# LED_IoT_Card.net
KiCad netlist of a schematic drawn in EAGLE
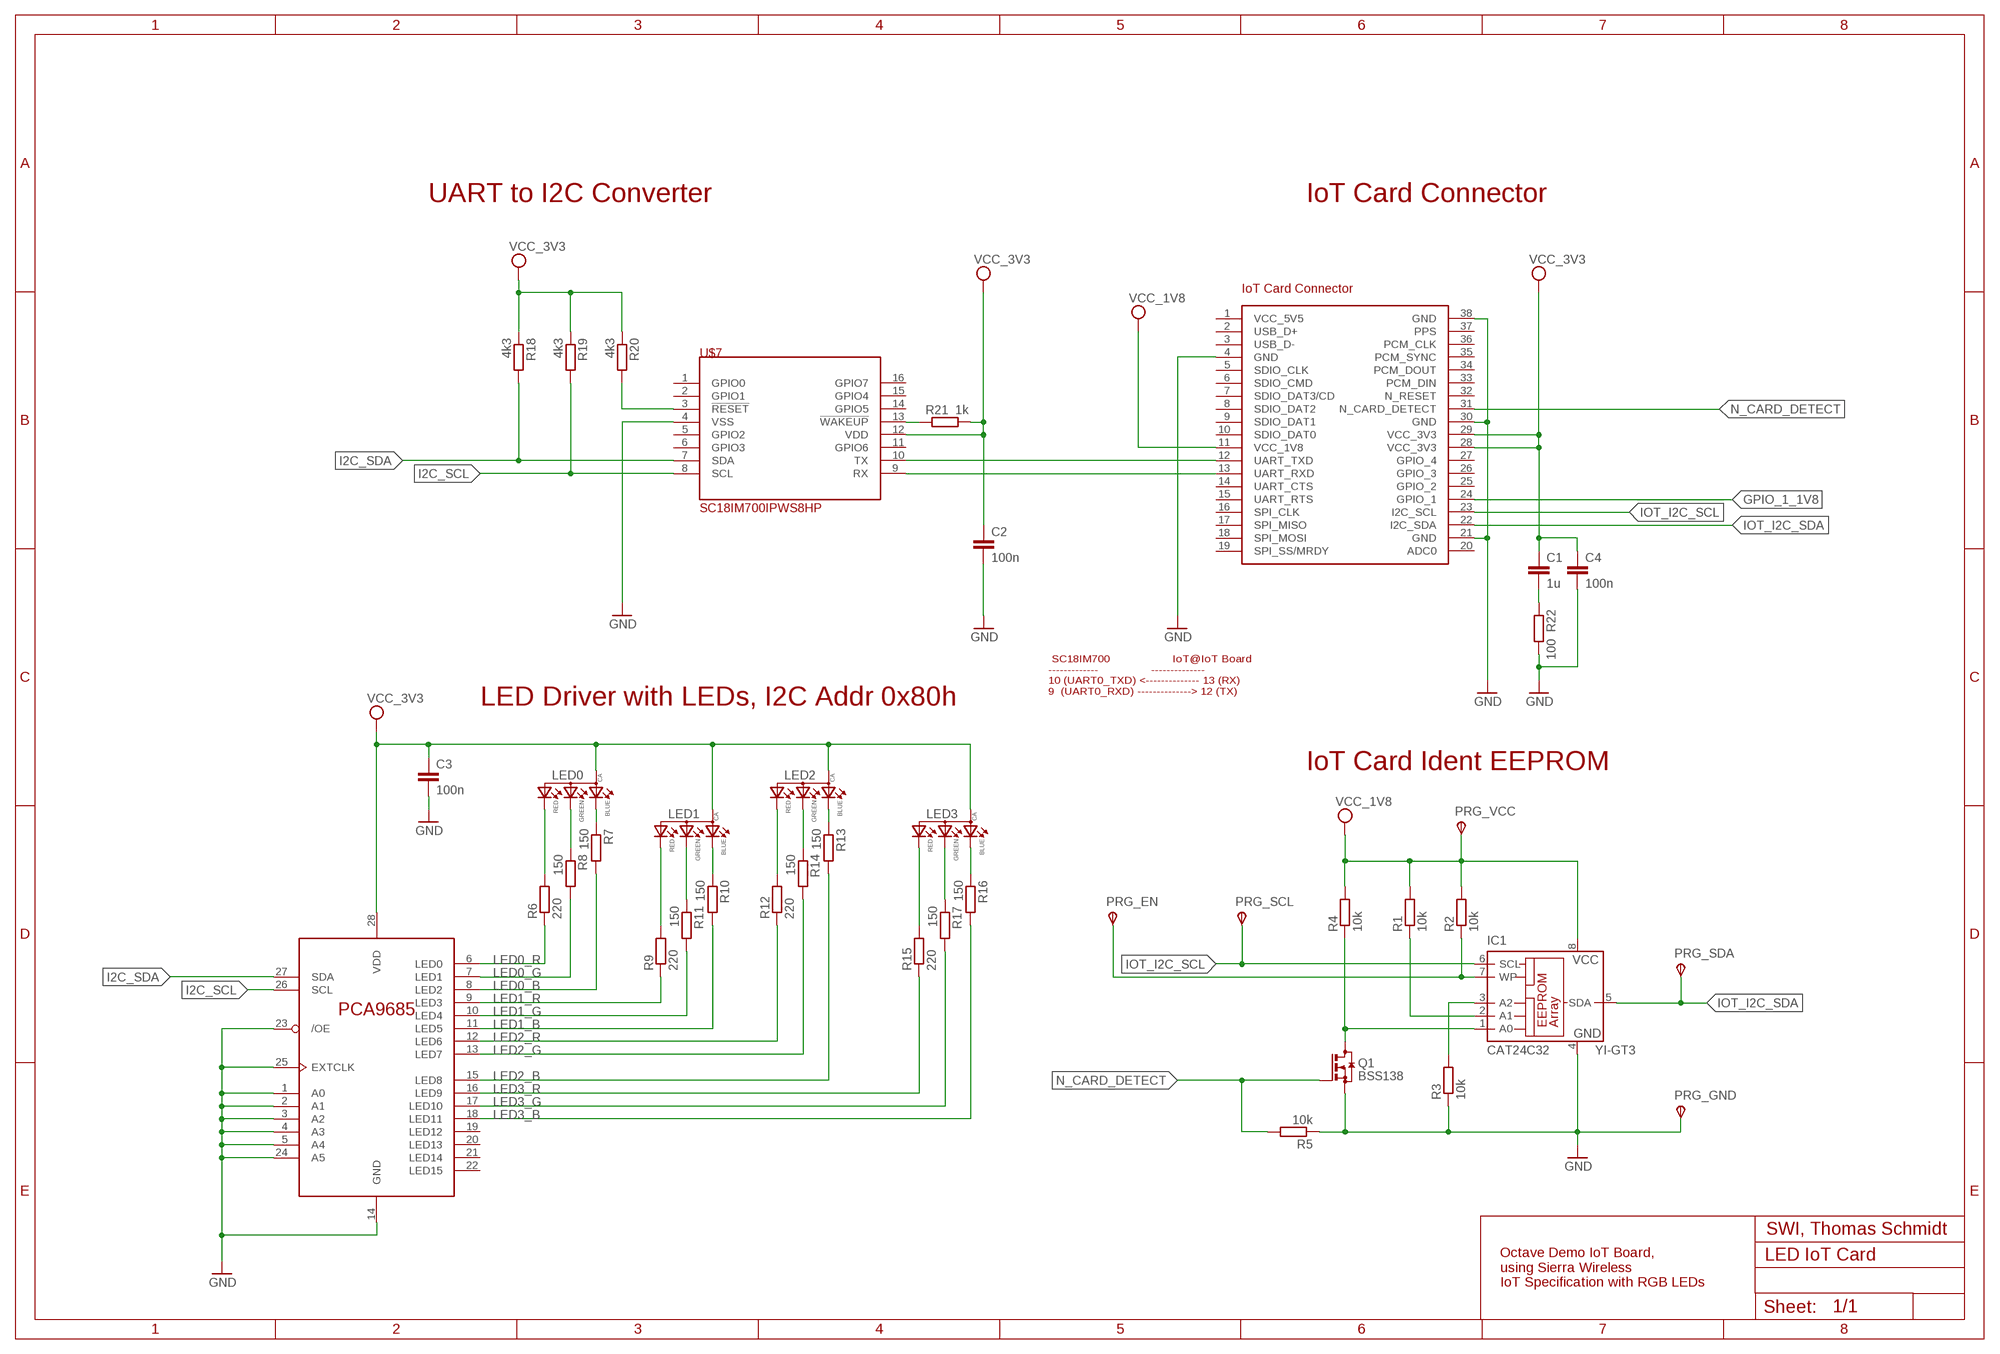
[diagram p0: schematic, sheet 1]

(export (version "E")
  (design (tool "Eeschema 10.0.6"))
  (components
    (comp (ref "C1")
      (value "1u")
      (footprint "eagle-import:C0805K")
      (libsource (lib "eagle-import") (part "C-EUC0805K"))
    )
    (comp (ref "C2")
      (value "100n")
      (footprint "eagle-import:C0603K")
      (libsource (lib "eagle-import") (part "C-EUC0603K"))
    )
    (comp (ref "C3")
      (value "100n")
      (footprint "eagle-import:C0603K")
      (libsource (lib "eagle-import") (part "C-EUC0603K"))
    )
    (comp (ref "C4")
      (value "100n")
      (footprint "eagle-import:C0603K")
      (libsource (lib "eagle-import") (part "C-EUC0603K"))
    )
    (comp (ref "IC1")
      (value "CAT24C32 YI-GT3")
      (footprint "eagle-import:TSSOP8")
      (fields (field (name "MPN") "CAT24C64YI-GT3"))
      (libsource (lib "eagle-import") (part "24STC64"))
    )
    (comp (ref "LED0")
      (value "0.13_RGB_LEDPLCC")
      (footprint "eagle-import:P-LCC-4-3")
      (libsource (lib "eagle-import") (part "0.13_RGB_LEDPLCC"))
    )
    (comp (ref "LED1")
      (value "0.13_RGB_LEDPLCC")
      (footprint "eagle-import:P-LCC-4-3")
      (libsource (lib "eagle-import") (part "0.13_RGB_LEDPLCC"))
    )
    (comp (ref "LED2")
      (value "0.13_RGB_LEDPLCC")
      (footprint "eagle-import:P-LCC-4-3")
      (libsource (lib "eagle-import") (part "0.13_RGB_LEDPLCC"))
    )
    (comp (ref "LED3")
      (value "0.13_RGB_LEDPLCC")
      (footprint "eagle-import:P-LCC-4-3")
      (libsource (lib "eagle-import") (part "0.13_RGB_LEDPLCC"))
    )
    (comp (ref "PRG_EN")
      (value "TPSB1,27")
      (footprint "eagle-import:B1,27")
      (libsource (lib "eagle-import") (part "TPSB1,27"))
    )
    (comp (ref "PRG_GND")
      (value "TPSB1,27")
      (footprint "eagle-import:B1,27")
      (libsource (lib "eagle-import") (part "TPSB1,27"))
    )
    (comp (ref "PRG_SCL")
      (value "TPSB1,27")
      (footprint "eagle-import:B1,27")
      (libsource (lib "eagle-import") (part "TPSB1,27"))
    )
    (comp (ref "PRG_SDA")
      (value "TPSB1,27")
      (footprint "eagle-import:B1,27")
      (libsource (lib "eagle-import") (part "TPSB1,27"))
    )
    (comp (ref "PRG_VCC")
      (value "TPSB1,27")
      (footprint "eagle-import:B1,27")
      (libsource (lib "eagle-import") (part "TPSB1,27"))
    )
    (comp (ref "Q1")
      (value "BSS138")
      (footprint "eagle-import:SOT23")
      (libsource (lib "eagle-import") (part "BSS123"))
    )
    (comp (ref "R1")
      (value "10k")
      (footprint "eagle-import:R0402")
      (libsource (lib "eagle-import") (part "R-EU_R0402"))
    )
    (comp (ref "R2")
      (value "10k")
      (footprint "eagle-import:R0402")
      (libsource (lib "eagle-import") (part "R-EU_R0402"))
    )
    (comp (ref "R3")
      (value "10k")
      (footprint "eagle-import:R0402")
      (libsource (lib "eagle-import") (part "R-EU_R0402"))
    )
    (comp (ref "R4")
      (value "10k")
      (footprint "eagle-import:R0402")
      (libsource (lib "eagle-import") (part "R-EU_R0402"))
    )
    (comp (ref "R5")
      (value "10k")
      (footprint "eagle-import:R0402")
      (libsource (lib "eagle-import") (part "R-EU_R0402"))
    )
    (comp (ref "R6")
      (value "220")
      (footprint "eagle-import:R0402")
      (libsource (lib "eagle-import") (part "R-EU_R0402"))
    )
    (comp (ref "R7")
      (value "150")
      (footprint "eagle-import:R0402")
      (libsource (lib "eagle-import") (part "R-EU_R0402"))
    )
    (comp (ref "R8")
      (value "150")
      (footprint "eagle-import:R0402")
      (libsource (lib "eagle-import") (part "R-EU_R0402"))
    )
    (comp (ref "R9")
      (value "220")
      (footprint "eagle-import:R0402")
      (libsource (lib "eagle-import") (part "R-EU_R0402"))
    )
    (comp (ref "R10")
      (value "150")
      (footprint "eagle-import:R0402")
      (libsource (lib "eagle-import") (part "R-EU_R0402"))
    )
    (comp (ref "R11")
      (value "150")
      (footprint "eagle-import:R0402")
      (libsource (lib "eagle-import") (part "R-EU_R0402"))
    )
    (comp (ref "R12")
      (value "220")
      (footprint "eagle-import:R0402")
      (libsource (lib "eagle-import") (part "R-EU_R0402"))
    )
    (comp (ref "R13")
      (value "150")
      (footprint "eagle-import:R0402")
      (libsource (lib "eagle-import") (part "R-EU_R0402"))
    )
    (comp (ref "R14")
      (value "150")
      (footprint "eagle-import:R0402")
      (libsource (lib "eagle-import") (part "R-EU_R0402"))
    )
    (comp (ref "R15")
      (value "220")
      (footprint "eagle-import:R0402")
      (libsource (lib "eagle-import") (part "R-EU_R0402"))
    )
    (comp (ref "R16")
      (value "150")
      (footprint "eagle-import:R0402")
      (libsource (lib "eagle-import") (part "R-EU_R0402"))
    )
    (comp (ref "R17")
      (value "150")
      (footprint "eagle-import:R0402")
      (libsource (lib "eagle-import") (part "R-EU_R0402"))
    )
    (comp (ref "R18")
      (value "4k3")
      (footprint "eagle-import:R0402")
      (libsource (lib "eagle-import") (part "R-EU_R0402"))
    )
    (comp (ref "R19")
      (value "4k3")
      (footprint "eagle-import:R0402")
      (libsource (lib "eagle-import") (part "R-EU_R0402"))
    )
    (comp (ref "R20")
      (value "4k3")
      (footprint "eagle-import:R0402")
      (libsource (lib "eagle-import") (part "R-EU_R0402"))
    )
    (comp (ref "R21")
      (value "1k")
      (footprint "eagle-import:R0402")
      (libsource (lib "eagle-import") (part "R-EU_R0402"))
    )
    (comp (ref "R22")
      (value "100")
      (footprint "eagle-import:R0402")
      (libsource (lib "eagle-import") (part "R-EU_R0402"))
    )
    (comp (ref "U$1")
      (value "IOTLONG")
      (footprint "eagle-import:IOT_LONG")
      (libsource (lib "eagle-import") (part "IOTLONG"))
    )
    (comp (ref "U$2")
      (value "PCA9685PW")
      (footprint "eagle-import:TSSOP28")
      (libsource (lib "eagle-import") (part "PCA9685PW"))
    )
    (comp (ref "U$7")
      (value "SC18IM700IPWS8HP")
      (footprint "eagle-import:TSSOP16")
      (libsource (lib "eagle-import") (part "SC18IM700IPWS8HP"))
    )
  )
  (nets
    (net (code "1") (name "/LED0_B") (class "Default")
      (node (ref "R7") (pin "2") (pinfunction "2_2") (pintype "passive"))
      (node (ref "U$2") (pin "8") (pinfunction "LED2_8") (pintype "bidirectional"))
    )
    (net (code "2") (name "/LED0_G") (class "Default")
      (node (ref "R8") (pin "2") (pinfunction "2_2") (pintype "passive"))
      (node (ref "U$2") (pin "7") (pinfunction "LED1_7") (pintype "bidirectional"))
    )
    (net (code "3") (name "/LED0_R") (class "Default")
      (node (ref "R6") (pin "1") (pinfunction "1_1") (pintype "passive"))
      (node (ref "U$2") (pin "6") (pinfunction "LED0_6") (pintype "bidirectional"))
    )
    (net (code "4") (name "/LED1_B") (class "Default")
      (node (ref "R10") (pin "2") (pinfunction "2_2") (pintype "passive"))
      (node (ref "U$2") (pin "11") (pinfunction "LED5_11") (pintype "bidirectional"))
    )
    (net (code "5") (name "/LED1_G") (class "Default")
      (node (ref "R11") (pin "2") (pinfunction "2_2") (pintype "passive"))
      (node (ref "U$2") (pin "10") (pinfunction "LED4_10") (pintype "bidirectional"))
    )
    (net (code "6") (name "/LED1_R") (class "Default")
      (node (ref "R9") (pin "1") (pinfunction "1_1") (pintype "passive"))
      (node (ref "U$2") (pin "9") (pinfunction "LED3_9") (pintype "bidirectional"))
    )
    (net (code "7") (name "/LED2_B") (class "Default")
      (node (ref "R13") (pin "2") (pinfunction "2_2") (pintype "passive"))
      (node (ref "U$2") (pin "15") (pinfunction "LED8_15") (pintype "bidirectional"))
    )
    (net (code "8") (name "/LED2_G") (class "Default")
      (node (ref "R14") (pin "2") (pinfunction "2_2") (pintype "passive"))
      (node (ref "U$2") (pin "13") (pinfunction "LED7_13") (pintype "bidirectional"))
    )
    (net (code "9") (name "/LED2_R") (class "Default")
      (node (ref "R12") (pin "1") (pinfunction "1_1") (pintype "passive"))
      (node (ref "U$2") (pin "12") (pinfunction "LED6_12") (pintype "bidirectional"))
    )
    (net (code "10") (name "/LED3_B") (class "Default")
      (node (ref "R16") (pin "2") (pinfunction "2_2") (pintype "passive"))
      (node (ref "U$2") (pin "18") (pinfunction "LED11_18") (pintype "bidirectional"))
    )
    (net (code "11") (name "/LED3_G") (class "Default")
      (node (ref "R17") (pin "2") (pinfunction "2_2") (pintype "passive"))
      (node (ref "U$2") (pin "17") (pinfunction "LED10_17") (pintype "bidirectional"))
    )
    (net (code "12") (name "/LED3_R") (class "Default")
      (node (ref "R15") (pin "1") (pinfunction "1_1") (pintype "passive"))
      (node (ref "U$2") (pin "16") (pinfunction "LED9_16") (pintype "bidirectional"))
    )
    (net (code "13") (name "/VCC_5V5") (class "Default")
      (node (ref "U$1") (pin "1") (pinfunction "VCC_5V5_1") (pintype "power_in"))
    )
    (net (code "14") (name "GND") (class "Default")
      (node (ref "C2") (pin "2") (pinfunction "2_2") (pintype "passive"))
      (node (ref "C3") (pin "2") (pinfunction "2_2") (pintype "passive"))
      (node (ref "C4") (pin "2") (pinfunction "2_2") (pintype "passive"))
      (node (ref "IC1") (pin "4") (pinfunction "GND_4") (pintype "power_in"))
      (node (ref "PRG_GND") (pin "TP") (pinfunction "PP_TP") (pintype "input"))
      (node (ref "Q1") (pin "2") (pinfunction "S_2") (pintype "passive"))
      (node (ref "R22") (pin "2") (pinfunction "2_2") (pintype "passive"))
      (node (ref "R3") (pin "1") (pinfunction "1_1") (pintype "passive"))
      (node (ref "R5") (pin "1") (pinfunction "1_1") (pintype "passive"))
      (node (ref "U$1") (pin "21") (pinfunction "GND_21") (pintype "power_in"))
      (node (ref "U$1") (pin "30") (pinfunction "GND_30") (pintype "power_in"))
      (node (ref "U$1") (pin "38") (pinfunction "GND_38") (pintype "bidirectional"))
      (node (ref "U$1") (pin "4") (pinfunction "GND_4") (pintype "power_in"))
      (node (ref "U$2") (pin "1") (pinfunction "A0_1") (pintype "bidirectional"))
      (node (ref "U$2") (pin "14") (pinfunction "GND_14") (pintype "power_in"))
      (node (ref "U$2") (pin "2") (pinfunction "A1_2") (pintype "bidirectional"))
      (node (ref "U$2") (pin "23") (pinfunction "/OE_23") (pintype "bidirectional"))
      (node (ref "U$2") (pin "24") (pinfunction "A5_24") (pintype "bidirectional"))
      (node (ref "U$2") (pin "25") (pinfunction "EXTCLK_25") (pintype "input"))
      (node (ref "U$2") (pin "3") (pinfunction "A2_3") (pintype "bidirectional"))
      (node (ref "U$2") (pin "4") (pinfunction "A3_4") (pintype "bidirectional"))
      (node (ref "U$2") (pin "5") (pinfunction "A4_5") (pintype "bidirectional"))
      (node (ref "U$7") (pin "4") (pinfunction "VSS_4") (pintype "power_in"))
    )
    (net (code "15") (name "GPIO_1_1V8") (class "Default")
      (node (ref "U$1") (pin "24") (pinfunction "GPIO_1_24") (pintype "bidirectional"))
    )
    (net (code "16") (name "I2C_SCL") (class "Default")
      (node (ref "R19") (pin "2") (pinfunction "2_2") (pintype "passive"))
      (node (ref "U$2") (pin "26") (pinfunction "SCL_26") (pintype "bidirectional"))
      (node (ref "U$7") (pin "8") (pinfunction "SCL_8") (pintype "bidirectional"))
    )
    (net (code "17") (name "I2C_SDA") (class "Default")
      (node (ref "R18") (pin "2") (pinfunction "2_2") (pintype "passive"))
      (node (ref "U$2") (pin "27") (pinfunction "SDA_27") (pintype "bidirectional"))
      (node (ref "U$7") (pin "7") (pinfunction "SDA_7") (pintype "bidirectional"))
    )
    (net (code "18") (name "IOT_I2C_SCL") (class "Default")
      (node (ref "IC1") (pin "6") (pinfunction "SCL_6") (pintype "input"))
      (node (ref "PRG_SCL") (pin "TP") (pinfunction "PP_TP") (pintype "input"))
      (node (ref "U$1") (pin "23") (pinfunction "I2C_SCL_23") (pintype "input"))
    )
    (net (code "19") (name "IOT_I2C_SDA") (class "Default")
      (node (ref "IC1") (pin "5") (pinfunction "SDA_5") (pintype "bidirectional"))
      (node (ref "PRG_SDA") (pin "TP") (pinfunction "PP_TP") (pintype "input"))
      (node (ref "U$1") (pin "22") (pinfunction "I2C_SDA_22") (pintype "bidirectional"))
    )
    (net (code "20") (name "N_CARD_DETECT") (class "Default")
      (node (ref "Q1") (pin "1") (pinfunction "G_1") (pintype "passive"))
      (node (ref "R5") (pin "2") (pinfunction "2_2") (pintype "passive"))
      (node (ref "U$1") (pin "31") (pinfunction "N_CARD_DETECT_31") (pintype "bidirectional"))
    )
    (net (code "21") (name "Net-(C1-Pad2)") (class "Default")
      (node (ref "C1") (pin "2") (pinfunction "2_2") (pintype "passive"))
      (node (ref "R22") (pin "1") (pinfunction "1_1") (pintype "passive"))
    )
    (net (code "22") (name "Net-(IC1-A0)") (class "Default")
      (node (ref "IC1") (pin "1") (pinfunction "A0_1") (pintype "input"))
      (node (ref "Q1") (pin "3") (pinfunction "D_3") (pintype "passive"))
      (node (ref "R4") (pin "1") (pinfunction "1_1") (pintype "passive"))
    )
    (net (code "23") (name "Net-(IC1-A1)") (class "Default")
      (node (ref "IC1") (pin "2") (pinfunction "A1_2") (pintype "input"))
      (node (ref "R1") (pin "1") (pinfunction "1_1") (pintype "passive"))
    )
    (net (code "24") (name "Net-(IC1-A2)") (class "Default")
      (node (ref "IC1") (pin "3") (pinfunction "A2_3") (pintype "input"))
      (node (ref "R3") (pin "2") (pinfunction "2_2") (pintype "passive"))
    )
    (net (code "25") (name "Net-(IC1-WP)") (class "Default")
      (node (ref "IC1") (pin "7") (pinfunction "WP_7") (pintype "input"))
      (node (ref "PRG_EN") (pin "TP") (pinfunction "PP_TP") (pintype "input"))
      (node (ref "R2") (pin "1") (pinfunction "1_1") (pintype "passive"))
    )
    (net (code "26") (name "Net-(LED0-BLUE)") (class "Default")
      (node (ref "LED0") (pin "3") (pinfunction "BLUE_3") (pintype "passive"))
      (node (ref "R7") (pin "1") (pinfunction "1_1") (pintype "passive"))
    )
    (net (code "27") (name "Net-(LED0-GREEN)") (class "Default")
      (node (ref "LED0") (pin "2") (pinfunction "GREEN_2") (pintype "passive"))
      (node (ref "R8") (pin "1") (pinfunction "1_1") (pintype "passive"))
    )
    (net (code "28") (name "Net-(LED0-RED)") (class "Default")
      (node (ref "LED0") (pin "1") (pinfunction "RED_1") (pintype "passive"))
      (node (ref "R6") (pin "2") (pinfunction "2_2") (pintype "passive"))
    )
    (net (code "29") (name "Net-(LED1-BLUE)") (class "Default")
      (node (ref "LED1") (pin "3") (pinfunction "BLUE_3") (pintype "passive"))
      (node (ref "R10") (pin "1") (pinfunction "1_1") (pintype "passive"))
    )
    (net (code "30") (name "Net-(LED1-GREEN)") (class "Default")
      (node (ref "LED1") (pin "2") (pinfunction "GREEN_2") (pintype "passive"))
      (node (ref "R11") (pin "1") (pinfunction "1_1") (pintype "passive"))
    )
    (net (code "31") (name "Net-(LED1-RED)") (class "Default")
      (node (ref "LED1") (pin "1") (pinfunction "RED_1") (pintype "passive"))
      (node (ref "R9") (pin "2") (pinfunction "2_2") (pintype "passive"))
    )
    (net (code "32") (name "Net-(LED2-BLUE)") (class "Default")
      (node (ref "LED2") (pin "3") (pinfunction "BLUE_3") (pintype "passive"))
      (node (ref "R13") (pin "1") (pinfunction "1_1") (pintype "passive"))
    )
    (net (code "33") (name "Net-(LED2-GREEN)") (class "Default")
      (node (ref "LED2") (pin "2") (pinfunction "GREEN_2") (pintype "passive"))
      (node (ref "R14") (pin "1") (pinfunction "1_1") (pintype "passive"))
    )
    (net (code "34") (name "Net-(LED2-RED)") (class "Default")
      (node (ref "LED2") (pin "1") (pinfunction "RED_1") (pintype "passive"))
      (node (ref "R12") (pin "2") (pinfunction "2_2") (pintype "passive"))
    )
    (net (code "35") (name "Net-(LED3-BLUE)") (class "Default")
      (node (ref "LED3") (pin "3") (pinfunction "BLUE_3") (pintype "passive"))
      (node (ref "R16") (pin "1") (pinfunction "1_1") (pintype "passive"))
    )
    (net (code "36") (name "Net-(LED3-GREEN)") (class "Default")
      (node (ref "LED3") (pin "2") (pinfunction "GREEN_2") (pintype "passive"))
      (node (ref "R17") (pin "1") (pinfunction "1_1") (pintype "passive"))
    )
    (net (code "37") (name "Net-(LED3-RED)") (class "Default")
      (node (ref "LED3") (pin "1") (pinfunction "RED_1") (pintype "passive"))
      (node (ref "R15") (pin "2") (pinfunction "2_2") (pintype "passive"))
    )
    (net (code "38") (name "Net-(U$1-UART_RXD)") (class "Default")
      (node (ref "U$1") (pin "13") (pinfunction "UART_RXD_13") (pintype "input"))
      (node (ref "U$7") (pin "9") (pinfunction "RX_9") (pintype "bidirectional"))
    )
    (net (code "39") (name "Net-(U$1-UART_TXD)") (class "Default")
      (node (ref "U$1") (pin "12") (pinfunction "UART_TXD_12") (pintype "output"))
      (node (ref "U$7") (pin "10") (pinfunction "TX_10") (pintype "bidirectional"))
    )
    (net (code "40") (name "Net-(U$7-~{RESET})") (class "Default")
      (node (ref "R20") (pin "2") (pinfunction "2_2") (pintype "passive"))
      (node (ref "U$7") (pin "3") (pinfunction "~{RESET}_3") (pintype "bidirectional"))
    )
    (net (code "41") (name "Net-(U$7-~{WAKEUP})") (class "Default")
      (node (ref "R21") (pin "1") (pinfunction "1_1") (pintype "passive"))
      (node (ref "U$7") (pin "13") (pinfunction "~{WAKEUP}_13") (pintype "bidirectional"))
    )
    (net (code "42") (name "VCC_1V8") (class "Default")
      (node (ref "IC1") (pin "8") (pinfunction "VCC_8") (pintype "power_in"))
      (node (ref "PRG_VCC") (pin "TP") (pinfunction "PP_TP") (pintype "input"))
      (node (ref "R1") (pin "2") (pinfunction "2_2") (pintype "passive"))
      (node (ref "R2") (pin "2") (pinfunction "2_2") (pintype "passive"))
      (node (ref "R4") (pin "2") (pinfunction "2_2") (pintype "passive"))
      (node (ref "U$1") (pin "11") (pinfunction "VCC_1V8_11") (pintype "power_in"))
    )
    (net (code "43") (name "VCC_3V3") (class "Default")
      (node (ref "C1") (pin "1") (pinfunction "1_1") (pintype "passive"))
      (node (ref "C2") (pin "1") (pinfunction "1_1") (pintype "passive"))
      (node (ref "C3") (pin "1") (pinfunction "1_1") (pintype "passive"))
      (node (ref "C4") (pin "1") (pinfunction "1_1") (pintype "passive"))
      (node (ref "LED0") (pin "4") (pinfunction "ANODE_4") (pintype "passive"))
      (node (ref "LED1") (pin "4") (pinfunction "ANODE_4") (pintype "passive"))
      (node (ref "LED2") (pin "4") (pinfunction "ANODE_4") (pintype "passive"))
      (node (ref "LED3") (pin "4") (pinfunction "ANODE_4") (pintype "passive"))
      (node (ref "R18") (pin "1") (pinfunction "1_1") (pintype "passive"))
      (node (ref "R19") (pin "1") (pinfunction "1_1") (pintype "passive"))
      (node (ref "R20") (pin "1") (pinfunction "1_1") (pintype "passive"))
      (node (ref "R21") (pin "2") (pinfunction "2_2") (pintype "passive"))
      (node (ref "U$1") (pin "28") (pinfunction "VCC_3V3_28") (pintype "power_in"))
      (node (ref "U$1") (pin "29") (pinfunction "VCC_3V3_29") (pintype "power_in"))
      (node (ref "U$2") (pin "28") (pinfunction "VDD_28") (pintype "power_in"))
      (node (ref "U$7") (pin "12") (pinfunction "VDD_12") (pintype "power_in"))
    )
    (net (code "44") (name "unconnected-(U$1-ADC0-Pad20)") (class "Default")
      (node (ref "U$1") (pin "20") (pinfunction "ADC0_20") (pintype "output"))
    )
    (net (code "45") (name "unconnected-(U$1-GPIO_2-Pad25)") (class "Default")
      (node (ref "U$1") (pin "25") (pinfunction "GPIO_2_25") (pintype "bidirectional"))
    )
    (net (code "46") (name "unconnected-(U$1-GPIO_3-Pad26)") (class "Default")
      (node (ref "U$1") (pin "26") (pinfunction "GPIO_3_26") (pintype "bidirectional"))
    )
    (net (code "47") (name "unconnected-(U$1-GPIO_4-Pad27)") (class "Default")
      (node (ref "U$1") (pin "27") (pinfunction "GPIO_4_27") (pintype "bidirectional"))
    )
    (net (code "48") (name "unconnected-(U$1-N_RESET-Pad32)") (class "Default")
      (node (ref "U$1") (pin "32") (pinfunction "N_RESET_32") (pintype "bidirectional"))
    )
    (net (code "49") (name "unconnected-(U$1-PCM_CLK-Pad36)") (class "Default")
      (node (ref "U$1") (pin "36") (pinfunction "PCM_CLK_36") (pintype "input"))
    )
    (net (code "50") (name "unconnected-(U$1-PCM_DIN-Pad33)") (class "Default")
      (node (ref "U$1") (pin "33") (pinfunction "PCM_DIN_33") (pintype "output"))
    )
    (net (code "51") (name "unconnected-(U$1-PCM_DOUT-Pad34)") (class "Default")
      (node (ref "U$1") (pin "34") (pinfunction "PCM_DOUT_34") (pintype "input"))
    )
    (net (code "52") (name "unconnected-(U$1-PCM_SYNC-Pad35)") (class "Default")
      (node (ref "U$1") (pin "35") (pinfunction "PCM_SYNC_35") (pintype "input"))
    )
    (net (code "53") (name "unconnected-(U$1-PPS-Pad37)") (class "Default")
      (node (ref "U$1") (pin "37") (pinfunction "PPS_37") (pintype "input"))
    )
    (net (code "54") (name "unconnected-(U$1-SDIO_CLK-Pad5)") (class "Default")
      (node (ref "U$1") (pin "5") (pinfunction "SDIO_CLK_5") (pintype "input"))
    )
    (net (code "55") (name "unconnected-(U$1-SDIO_CMD-Pad6)") (class "Default")
      (node (ref "U$1") (pin "6") (pinfunction "SDIO_CMD_6") (pintype "input"))
    )
    (net (code "56") (name "unconnected-(U$1-SDIO_DAT0-Pad10)") (class "Default")
      (node (ref "U$1") (pin "10") (pinfunction "SDIO_DAT0_10") (pintype "bidirectional"))
    )
    (net (code "57") (name "unconnected-(U$1-SDIO_DAT1-Pad9)") (class "Default")
      (node (ref "U$1") (pin "9") (pinfunction "SDIO_DAT1_9") (pintype "bidirectional"))
    )
    (net (code "58") (name "unconnected-(U$1-SDIO_DAT2-Pad8)") (class "Default")
      (node (ref "U$1") (pin "8") (pinfunction "SDIO_DAT2_8") (pintype "bidirectional"))
    )
    (net (code "59") (name "unconnected-(U$1-SDIO_DAT3{slash}CD-Pad7)") (class "Default")
      (node (ref "U$1") (pin "7") (pinfunction "SDIO_DAT3/CD_7") (pintype "bidirectional"))
    )
    (net (code "60") (name "unconnected-(U$1-SPI_CLK-Pad16)") (class "Default")
      (node (ref "U$1") (pin "16") (pinfunction "SPI_CLK_16") (pintype "input"))
    )
    (net (code "61") (name "unconnected-(U$1-SPI_MISO-Pad17)") (class "Default")
      (node (ref "U$1") (pin "17") (pinfunction "SPI_MISO_17") (pintype "output"))
    )
    (net (code "62") (name "unconnected-(U$1-SPI_MOSI-Pad18)") (class "Default")
      (node (ref "U$1") (pin "18") (pinfunction "SPI_MOSI_18") (pintype "input"))
    )
    (net (code "63") (name "unconnected-(U$1-SPI_SS{slash}MRDY-Pad19)") (class "Default")
      (node (ref "U$1") (pin "19") (pinfunction "SPI_SS/MRDY_19") (pintype "input"))
    )
    (net (code "64") (name "unconnected-(U$1-UART_CTS-Pad14)") (class "Default")
      (node (ref "U$1") (pin "14") (pinfunction "UART_CTS_14") (pintype "input"))
    )
    (net (code "65") (name "unconnected-(U$1-UART_RTS-Pad15)") (class "Default")
      (node (ref "U$1") (pin "15") (pinfunction "UART_RTS_15") (pintype "output"))
    )
    (net (code "66") (name "unconnected-(U$1-USB_D+-Pad2)") (class "Default")
      (node (ref "U$1") (pin "2") (pinfunction "USB_D+_2") (pintype "bidirectional"))
    )
    (net (code "67") (name "unconnected-(U$1-USB_D--Pad3)") (class "Default")
      (node (ref "U$1") (pin "3") (pinfunction "USB_D-_3") (pintype "bidirectional"))
    )
    (net (code "68") (name "unconnected-(U$2-LED12-Pad19)") (class "Default")
      (node (ref "U$2") (pin "19") (pinfunction "LED12_19") (pintype "bidirectional"))
    )
    (net (code "69") (name "unconnected-(U$2-LED13-Pad20)") (class "Default")
      (node (ref "U$2") (pin "20") (pinfunction "LED13_20") (pintype "bidirectional"))
    )
    (net (code "70") (name "unconnected-(U$2-LED14-Pad21)") (class "Default")
      (node (ref "U$2") (pin "21") (pinfunction "LED14_21") (pintype "bidirectional"))
    )
    (net (code "71") (name "unconnected-(U$2-LED15-Pad22)") (class "Default")
      (node (ref "U$2") (pin "22") (pinfunction "LED15_22") (pintype "bidirectional"))
    )
    (net (code "72") (name "unconnected-(U$7-GPIO0-Pad1)") (class "Default")
      (node (ref "U$7") (pin "1") (pinfunction "GPIO0_1") (pintype "bidirectional"))
    )
    (net (code "73") (name "unconnected-(U$7-GPIO1-Pad2)") (class "Default")
      (node (ref "U$7") (pin "2") (pinfunction "GPIO1_2") (pintype "bidirectional"))
    )
    (net (code "74") (name "unconnected-(U$7-GPIO2-Pad5)") (class "Default")
      (node (ref "U$7") (pin "5") (pinfunction "GPIO2_5") (pintype "bidirectional"))
    )
    (net (code "75") (name "unconnected-(U$7-GPIO3-Pad6)") (class "Default")
      (node (ref "U$7") (pin "6") (pinfunction "GPIO3_6") (pintype "bidirectional"))
    )
    (net (code "76") (name "unconnected-(U$7-GPIO4-Pad15)") (class "Default")
      (node (ref "U$7") (pin "15") (pinfunction "GPIO4_15") (pintype "bidirectional"))
    )
    (net (code "77") (name "unconnected-(U$7-GPIO5-Pad14)") (class "Default")
      (node (ref "U$7") (pin "14") (pinfunction "GPIO5_14") (pintype "bidirectional"))
    )
    (net (code "78") (name "unconnected-(U$7-GPIO6-Pad11)") (class "Default")
      (node (ref "U$7") (pin "11") (pinfunction "GPIO6_11") (pintype "bidirectional"))
    )
    (net (code "79") (name "unconnected-(U$7-GPIO7-Pad16)") (class "Default")
      (node (ref "U$7") (pin "16") (pinfunction "GPIO7_16") (pintype "bidirectional"))
    )
  )
)
